# Steuerung.net
KiCad netlist of a schematic drawn in EAGLE
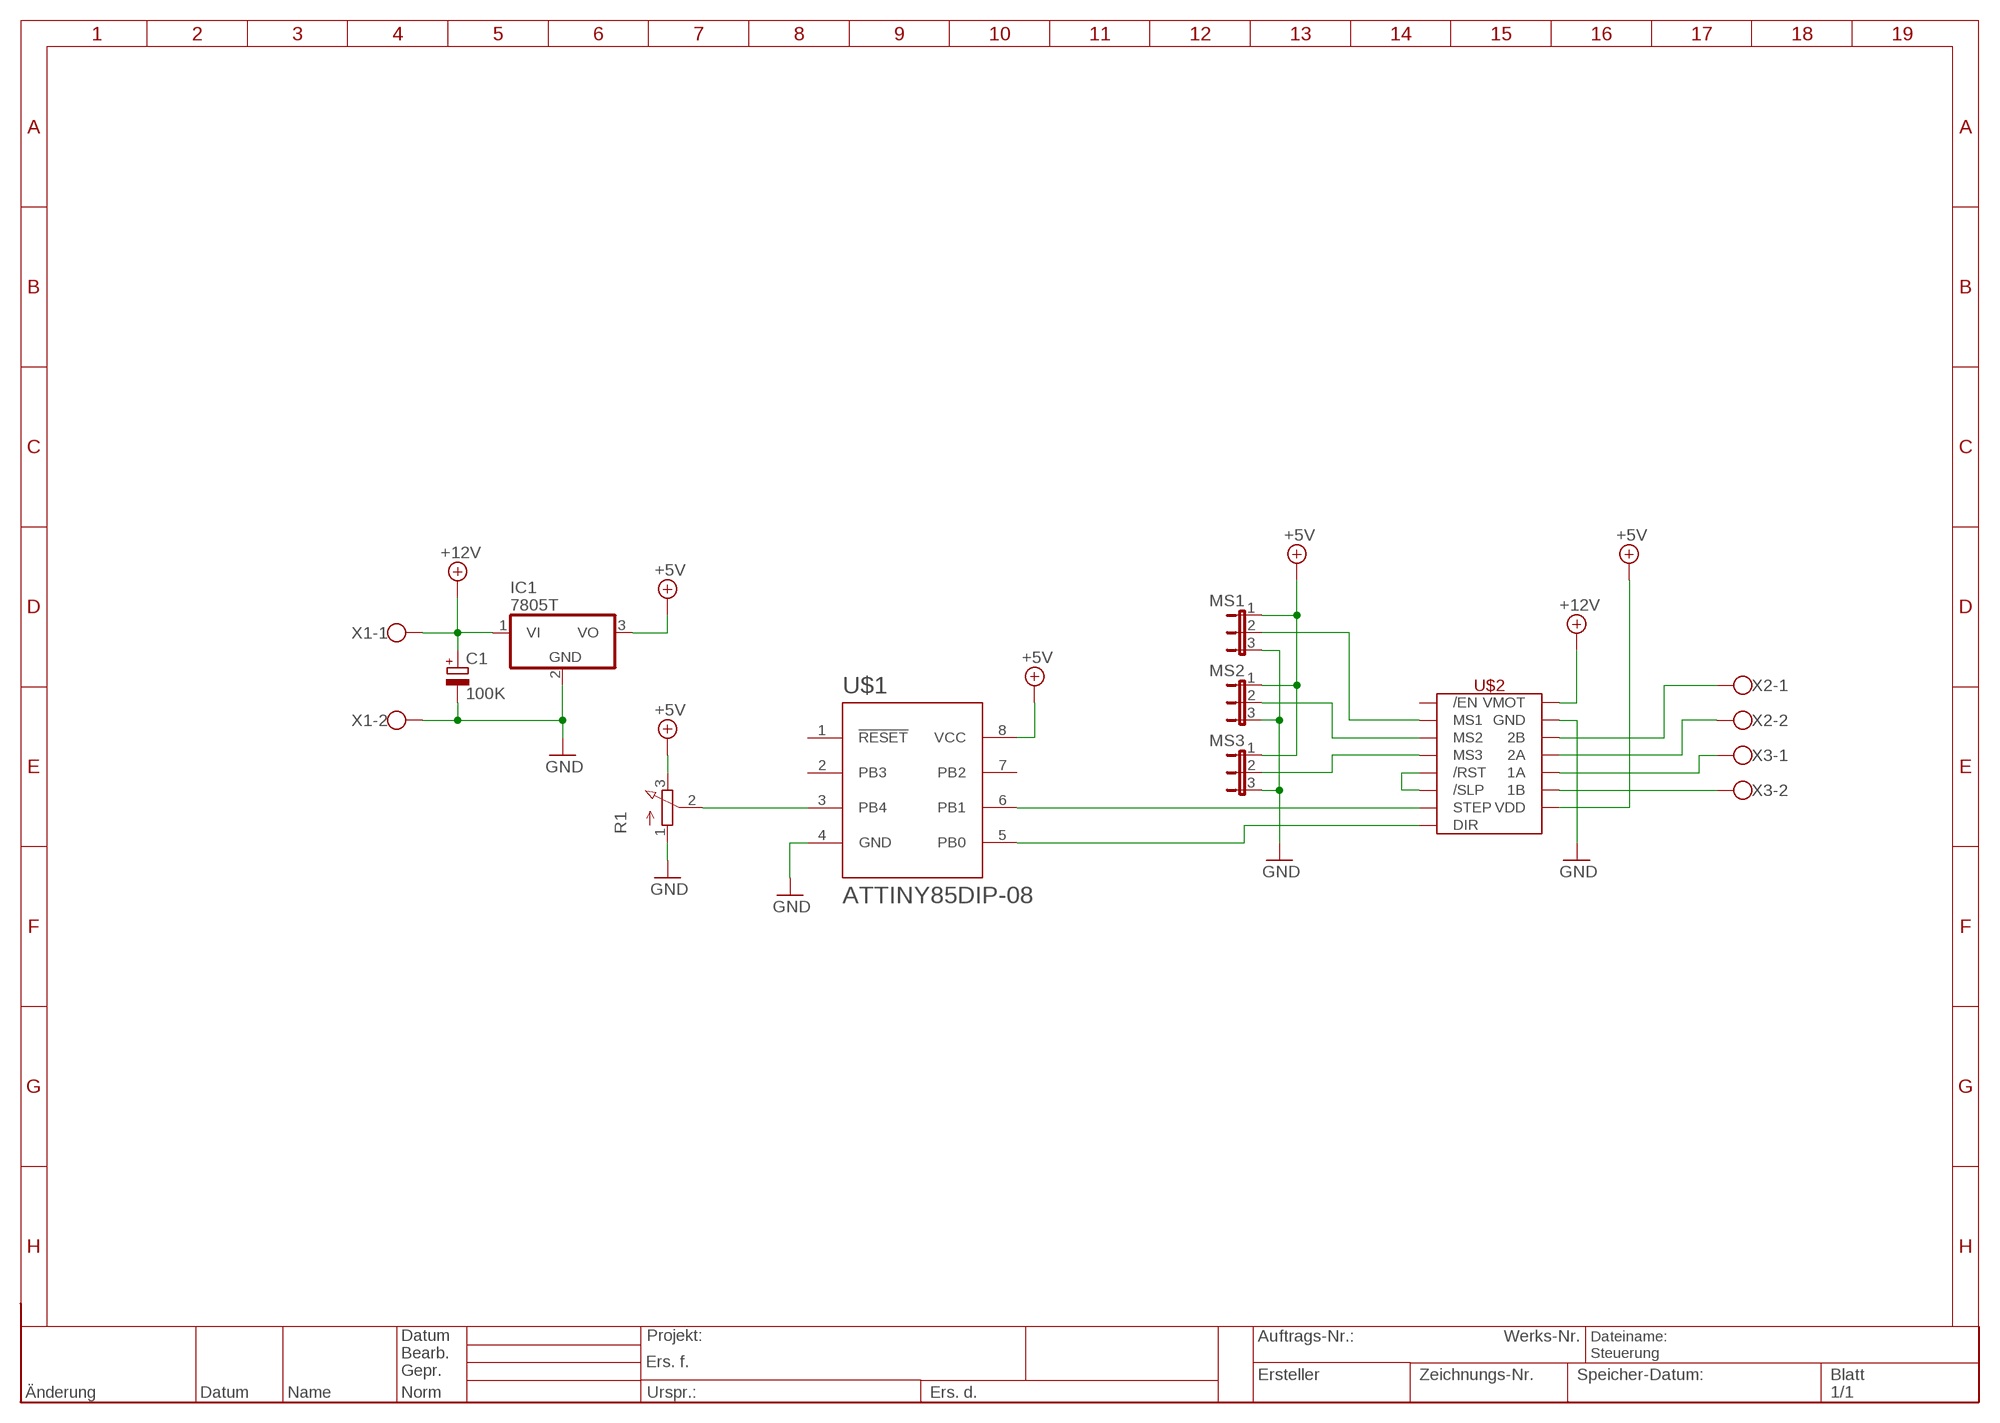
[diagram p0: schematic, sheet 1]

(export (version "E")
  (design (tool "Eeschema 10.0.6"))
  (components
    (comp (ref "C1")
      (value "100K")
      (footprint "eagle-import:E2-5")
      (libsource (lib "eagle-import") (part "CPOL-EUE2-5"))
    )
    (comp (ref "IC1")
      (value "7805T")
      (footprint "eagle-import:TO220H")
      (libsource (lib "eagle-import") (part "78T05"))
    )
    (comp (ref "MS1")
      (value "JP2E")
      (footprint "eagle-import:JP2")
      (libsource (lib "eagle-import") (part "JP2E"))
    )
    (comp (ref "MS2")
      (value "JP2E")
      (footprint "eagle-import:JP2")
      (libsource (lib "eagle-import") (part "JP2E"))
    )
    (comp (ref "MS3")
      (value "JP2E")
      (footprint "eagle-import:JP2")
      (libsource (lib "eagle-import") (part "JP2E"))
    )
    (comp (ref "R1")
      (value "3RP/1610N")
      (footprint "eagle-import:3RP_1610N")
      (libsource (lib "eagle-import") (part "3RP/1610N"))
    )
    (comp (ref "U$1")
      (value "ATTINY85DIP-08")
      (footprint "eagle-import:DIP900W57P254L920H431Q8B")
      (libsource (lib "eagle-import") (part "ATTINY85DIP-08"))
    )
    (comp (ref "U$2")
      (value "A4988_STEP")
      (footprint "eagle-import:A4988_STEP")
      (libsource (lib "eagle-import") (part "A4988_STEP"))
    )
    (comp (ref "X1")
      (value "W237-102")
      (footprint "eagle-import:W237-102")
      (fields (field (name "MPN") "237-102"))
      (libsource (lib "eagle-import") (part "W237-102"))
    )
    (comp (ref "X2")
      (value "W237-102")
      (footprint "eagle-import:W237-102")
      (fields (field (name "MPN") "237-102"))
      (libsource (lib "eagle-import") (part "W237-102"))
    )
    (comp (ref "X3")
      (value "W237-102")
      (footprint "eagle-import:W237-102")
      (fields (field (name "MPN") "237-102"))
      (libsource (lib "eagle-import") (part "W237-102"))
    )
  )
  (nets
    (net (code "1") (name "+5V") (class "Default")
      (node (ref "IC1") (pin "3") (pinfunction "VO_3") (pintype "passive"))
      (node (ref "MS1") (pin "1") (pinfunction "1_1") (pintype "passive"))
      (node (ref "MS2") (pin "1") (pinfunction "1_1") (pintype "passive"))
      (node (ref "MS3") (pin "1") (pinfunction "1_1") (pintype "passive"))
      (node (ref "R1") (pin "3") (pinfunction "E_3") (pintype "passive"))
      (node (ref "U$1") (pin "8") (pinfunction "VCC_8") (pintype "bidirectional"))
      (node (ref "U$2") (pin "VDD") (pinfunction "VDD_VDD") (pintype "bidirectional"))
    )
    (net (code "2") (name "+12V") (class "Default")
      (node (ref "C1") (pin "+") (pinfunction "+_+") (pintype "passive"))
      (node (ref "IC1") (pin "1") (pinfunction "VI_1") (pintype "input"))
      (node (ref "U$2") (pin "VMOT") (pinfunction "VMOT_VMOT") (pintype "bidirectional"))
      (node (ref "X1") (pin "1") (pinfunction "KL_1") (pintype "passive"))
    )
    (net (code "3") (name "GND") (class "Default")
      (node (ref "C1") (pin "-") (pinfunction "-_-") (pintype "passive"))
      (node (ref "IC1") (pin "2") (pinfunction "GND_2") (pintype "passive"))
      (node (ref "MS1") (pin "3") (pinfunction "3_3") (pintype "passive"))
      (node (ref "MS2") (pin "3") (pinfunction "3_3") (pintype "passive"))
      (node (ref "MS3") (pin "3") (pinfunction "3_3") (pintype "passive"))
      (node (ref "R1") (pin "1") (pinfunction "A_1") (pintype "passive"))
      (node (ref "U$1") (pin "4") (pinfunction "GND_4") (pintype "bidirectional"))
      (node (ref "U$2") (pin "GND") (pinfunction "GND_GND") (pintype "bidirectional"))
      (node (ref "U$2") (pin "GND2") (pinfunction "GND_GND2") (pintype "bidirectional"))
      (node (ref "X1") (pin "2") (pinfunction "KL_2") (pintype "passive"))
    )
    (net (code "4") (name "Net-(MS1-Pad2)") (class "Default")
      (node (ref "MS1") (pin "2") (pinfunction "2_2") (pintype "passive"))
      (node (ref "U$2") (pin "MS1") (pinfunction "MS1_MS1") (pintype "bidirectional"))
    )
    (net (code "5") (name "Net-(MS2-Pad2)") (class "Default")
      (node (ref "MS2") (pin "2") (pinfunction "2_2") (pintype "passive"))
      (node (ref "U$2") (pin "MS2") (pinfunction "MS2_MS2") (pintype "bidirectional"))
    )
    (net (code "6") (name "Net-(MS3-Pad2)") (class "Default")
      (node (ref "MS3") (pin "2") (pinfunction "2_2") (pintype "passive"))
      (node (ref "U$2") (pin "MS3") (pinfunction "MS3_MS3") (pintype "bidirectional"))
    )
    (net (code "7") (name "Net-(R1-S)") (class "Default")
      (node (ref "R1") (pin "2") (pinfunction "S_2") (pintype "passive"))
      (node (ref "U$1") (pin "3") (pinfunction "PB4_3") (pintype "bidirectional"))
    )
    (net (code "8") (name "Net-(U$1-PB0)") (class "Default")
      (node (ref "U$1") (pin "5") (pinfunction "PB0_5") (pintype "bidirectional"))
      (node (ref "U$2") (pin "DIR") (pinfunction "DIR_DIR") (pintype "bidirectional"))
    )
    (net (code "9") (name "Net-(U$1-PB1)") (class "Default")
      (node (ref "U$1") (pin "6") (pinfunction "PB1_6") (pintype "bidirectional"))
      (node (ref "U$2") (pin "STEP") (pinfunction "STEP_STEP") (pintype "bidirectional"))
    )
    (net (code "10") (name "Net-(U$2-Pad{slash}RST)") (class "Default")
      (node (ref "U$2") (pin "/RST") (pinfunction "/RST_/RST") (pintype "bidirectional"))
      (node (ref "U$2") (pin "/SLP") (pinfunction "/SLP_/SLP") (pintype "bidirectional"))
    )
    (net (code "11") (name "Net-(X2A-KL)") (class "Default")
      (node (ref "U$2") (pin "2B") (pinfunction "2B_2B") (pintype "bidirectional"))
      (node (ref "X2") (pin "1") (pinfunction "KL_1") (pintype "passive"))
    )
    (net (code "12") (name "Net-(X2B-KL)") (class "Default")
      (node (ref "U$2") (pin "2A") (pinfunction "2A_2A") (pintype "bidirectional"))
      (node (ref "X2") (pin "2") (pinfunction "KL_2") (pintype "passive"))
    )
    (net (code "13") (name "Net-(X3A-KL)") (class "Default")
      (node (ref "U$2") (pin "1A") (pinfunction "1A_1A") (pintype "bidirectional"))
      (node (ref "X3") (pin "1") (pinfunction "KL_1") (pintype "passive"))
    )
    (net (code "14") (name "Net-(X3B-KL)") (class "Default")
      (node (ref "U$2") (pin "1B") (pinfunction "1B_1B") (pintype "bidirectional"))
      (node (ref "X3") (pin "2") (pinfunction "KL_2") (pintype "passive"))
    )
    (net (code "15") (name "unconnected-(U$1-PB2-Pad7)") (class "Default")
      (node (ref "U$1") (pin "7") (pinfunction "PB2_7") (pintype "bidirectional"))
    )
    (net (code "16") (name "unconnected-(U$1-PB3-Pad2)") (class "Default")
      (node (ref "U$1") (pin "2") (pinfunction "PB3_2") (pintype "bidirectional"))
    )
    (net (code "17") (name "unconnected-(U$1-~{RESET}-Pad1)") (class "Default")
      (node (ref "U$1") (pin "1") (pinfunction "~{RESET}_1") (pintype "bidirectional"))
    )
    (net (code "18") (name "unconnected-(U$2-Pad{slash}EN)") (class "Default")
      (node (ref "U$2") (pin "/EN") (pinfunction "/EN_/EN") (pintype "bidirectional"))
    )
  )
)
